# ir_transmitter.net
KiCad netlist of a schematic drawn in EAGLE
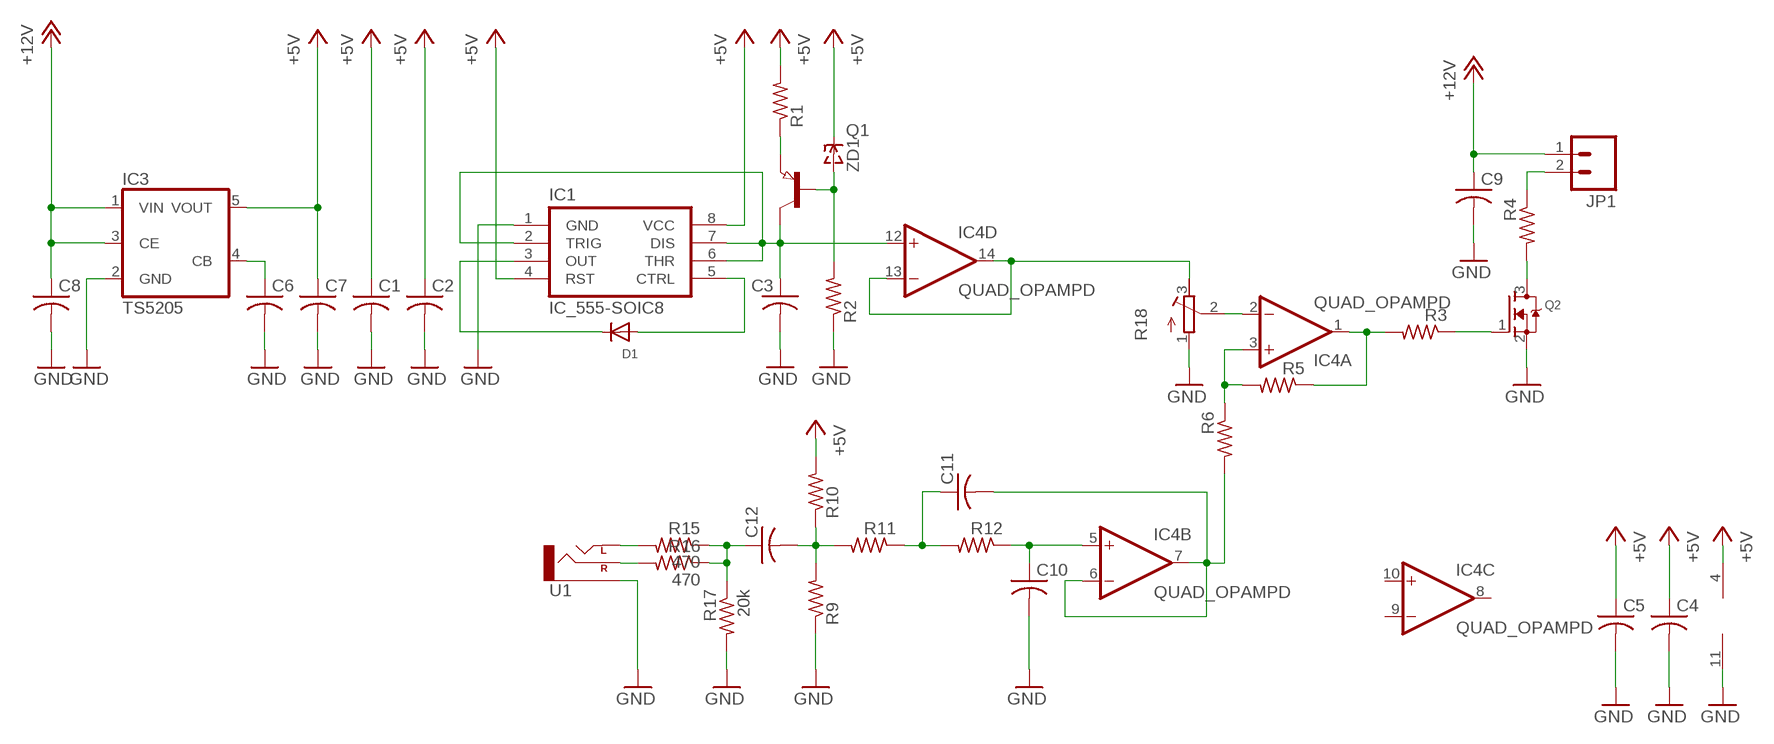
[diagram p0: schematic, sheet 1]

(export (version "E")
  (design (tool "Eeschema 10.0.6"))
  (components
    (comp (ref "C1")
      (value "C-USC1206")
      (footprint "eagle-import:C1206")
      (libsource (lib "eagle-import") (part "C-USC1206"))
    )
    (comp (ref "C2")
      (value "C-USC1206")
      (footprint "eagle-import:C1206")
      (libsource (lib "eagle-import") (part "C-USC1206"))
    )
    (comp (ref "C3")
      (value "C-USC1206")
      (footprint "eagle-import:C1206")
      (libsource (lib "eagle-import") (part "C-USC1206"))
    )
    (comp (ref "C4")
      (value "C-USC1206")
      (footprint "eagle-import:C1206")
      (libsource (lib "eagle-import") (part "C-USC1206"))
    )
    (comp (ref "C5")
      (value "C-USC1206")
      (footprint "eagle-import:C1206")
      (libsource (lib "eagle-import") (part "C-USC1206"))
    )
    (comp (ref "C6")
      (value "C-USC1206")
      (footprint "eagle-import:C1206")
      (libsource (lib "eagle-import") (part "C-USC1206"))
    )
    (comp (ref "C7")
      (value "C-USC1206")
      (footprint "eagle-import:C1206")
      (libsource (lib "eagle-import") (part "C-USC1206"))
    )
    (comp (ref "C8")
      (value "C-USC1206")
      (footprint "eagle-import:C1206")
      (libsource (lib "eagle-import") (part "C-USC1206"))
    )
    (comp (ref "C9")
      (value "C-USC1206")
      (footprint "eagle-import:C1206")
      (libsource (lib "eagle-import") (part "C-USC1206"))
    )
    (comp (ref "C10")
      (value "C-USC1206")
      (footprint "eagle-import:C1206")
      (libsource (lib "eagle-import") (part "C-USC1206"))
    )
    (comp (ref "C11")
      (value "C-USC1206")
      (footprint "eagle-import:C1206")
      (libsource (lib "eagle-import") (part "C-USC1206"))
    )
    (comp (ref "C12")
      (value "C-USC1206")
      (footprint "eagle-import:C1206")
      (libsource (lib "eagle-import") (part "C-USC1206"))
    )
    (comp (ref "D1")
      (value "DIODESOD-123")
      (footprint "eagle-import:SOD-123")
      (libsource (lib "eagle-import") (part "DIODESOD-123"))
    )
    (comp (ref "IC1")
      (value "IC_555-SOIC8")
      (footprint "eagle-import:SOIC-8")
      (libsource (lib "eagle-import") (part "IC_555-SOIC8"))
    )
    (comp (ref "IC3")
      (value "TS5205")
      (footprint "eagle-import:SOT25")
      (libsource (lib "eagle-import") (part "TS5205"))
    )
    (comp (ref "IC4")
      (value "QUAD_OPAMPD")
      (footprint "eagle-import:SO14")
      (libsource (lib "eagle-import") (part "QUAD_OPAMPD"))
    )
    (comp (ref "JP1")
      (value "M02POLAR")
      (footprint "eagle-import:MOLEX-1X2")
      (libsource (lib "eagle-import") (part "M02POLAR"))
    )
    (comp (ref "Q1")
      (value "PNP-TRANSISTOR_SOT23")
      (footprint "eagle-import:SOT23")
      (libsource (lib "eagle-import") (part "PNP-TRANSISTOR_SOT23"))
    )
    (comp (ref "Q2")
      (value "MOSFET-NREFLOW")
      (footprint "eagle-import:SOT23")
      (libsource (lib "eagle-import") (part "MOSFET-NREFLOW"))
    )
    (comp (ref "R1")
      (value "R-US_M1206")
      (footprint "eagle-import:M1206")
      (libsource (lib "eagle-import") (part "R-US_M1206"))
    )
    (comp (ref "R2")
      (value "R-US_M1206")
      (footprint "eagle-import:M1206")
      (libsource (lib "eagle-import") (part "R-US_M1206"))
    )
    (comp (ref "R3")
      (value "R-US_M1206")
      (footprint "eagle-import:M1206")
      (libsource (lib "eagle-import") (part "R-US_M1206"))
    )
    (comp (ref "R4")
      (value "R-US_M1206")
      (footprint "eagle-import:M1206")
      (libsource (lib "eagle-import") (part "R-US_M1206"))
    )
    (comp (ref "R5")
      (value "R-US_M1206")
      (footprint "eagle-import:M1206")
      (libsource (lib "eagle-import") (part "R-US_M1206"))
    )
    (comp (ref "R6")
      (value "R-US_M1206")
      (footprint "eagle-import:M1206")
      (libsource (lib "eagle-import") (part "R-US_M1206"))
    )
    (comp (ref "R9")
      (value "R-US_M1206")
      (footprint "eagle-import:M1206")
      (libsource (lib "eagle-import") (part "R-US_M1206"))
    )
    (comp (ref "R10")
      (value "R-US_M1206")
      (footprint "eagle-import:M1206")
      (libsource (lib "eagle-import") (part "R-US_M1206"))
    )
    (comp (ref "R11")
      (value "R-US_M1206")
      (footprint "eagle-import:M1206")
      (libsource (lib "eagle-import") (part "R-US_M1206"))
    )
    (comp (ref "R12")
      (value "R-US_M1206")
      (footprint "eagle-import:M1206")
      (libsource (lib "eagle-import") (part "R-US_M1206"))
    )
    (comp (ref "R15")
      (value "470")
      (footprint "eagle-import:M1206")
      (libsource (lib "eagle-import") (part "R-US_M1206"))
    )
    (comp (ref "R16")
      (value "470")
      (footprint "eagle-import:M1206")
      (libsource (lib "eagle-import") (part "R-US_M1206"))
    )
    (comp (ref "R17")
      (value "20k")
      (footprint "eagle-import:M1206")
      (libsource (lib "eagle-import") (part "R-US_M1206"))
    )
    (comp (ref "R18")
      (value "R-TRIMM3304W")
      (footprint "eagle-import:RTRIM3304W")
      (libsource (lib "eagle-import") (part "R-TRIMM3304W"))
    )
    (comp (ref "U1")
      (value "AUDIO-JACKSMD")
      (footprint "eagle-import:STEREOJACK2.5MM_SMD")
      (libsource (lib "eagle-import") (part "AUDIO-JACKSMD"))
    )
    (comp (ref "ZD1")
      (value "ZENERSOD-123")
      (footprint "eagle-import:SOD-123")
      (libsource (lib "eagle-import") (part "ZENERSOD-123"))
    )
  )
  (nets
    (net (code "1") (name "+5V") (class "Default")
      (node (ref "C1") (pin "1") (pinfunction "1_1") (pintype "passive"))
      (node (ref "C2") (pin "1") (pinfunction "1_1") (pintype "passive"))
      (node (ref "C4") (pin "1") (pinfunction "1_1") (pintype "passive"))
      (node (ref "C5") (pin "1") (pinfunction "1_1") (pintype "passive"))
      (node (ref "C7") (pin "1") (pinfunction "1_1") (pintype "passive"))
      (node (ref "IC1") (pin "4") (pinfunction "RST_4") (pintype "input"))
      (node (ref "IC1") (pin "8") (pinfunction "VCC_8") (pintype "power_in"))
      (node (ref "IC3") (pin "5") (pinfunction "VOUT_5") (pintype "passive"))
      (node (ref "IC4") (pin "4") (pinfunction "V+_4") (pintype "power_in"))
      (node (ref "R1") (pin "2") (pinfunction "2_2") (pintype "passive"))
      (node (ref "R10") (pin "2") (pinfunction "2_2") (pintype "passive"))
      (node (ref "ZD1") (pin "C") (pinfunction "C_C") (pintype "passive"))
    )
    (net (code "2") (name "+12V") (class "Default")
      (node (ref "C8") (pin "1") (pinfunction "1_1") (pintype "passive"))
      (node (ref "C9") (pin "1") (pinfunction "1_1") (pintype "passive"))
      (node (ref "IC3") (pin "1") (pinfunction "VIN_1") (pintype "input"))
      (node (ref "IC3") (pin "3") (pinfunction "CE_3") (pintype "input"))
      (node (ref "JP1") (pin "1") (pinfunction "1_1") (pintype "passive"))
    )
    (net (code "3") (name "GND") (class "Default")
      (node (ref "C1") (pin "2") (pinfunction "2_2") (pintype "passive"))
      (node (ref "C10") (pin "2") (pinfunction "2_2") (pintype "passive"))
      (node (ref "C2") (pin "2") (pinfunction "2_2") (pintype "passive"))
      (node (ref "C3") (pin "2") (pinfunction "2_2") (pintype "passive"))
      (node (ref "C4") (pin "2") (pinfunction "2_2") (pintype "passive"))
      (node (ref "C5") (pin "2") (pinfunction "2_2") (pintype "passive"))
      (node (ref "C6") (pin "2") (pinfunction "2_2") (pintype "passive"))
      (node (ref "C7") (pin "2") (pinfunction "2_2") (pintype "passive"))
      (node (ref "C8") (pin "2") (pinfunction "2_2") (pintype "passive"))
      (node (ref "C9") (pin "2") (pinfunction "2_2") (pintype "passive"))
      (node (ref "IC1") (pin "1") (pinfunction "GND_1") (pintype "power_in"))
      (node (ref "IC3") (pin "2") (pinfunction "GND_2") (pintype "passive"))
      (node (ref "IC4") (pin "11") (pinfunction "V-_11") (pintype "power_in"))
      (node (ref "Q2") (pin "2") (pinfunction "S_2") (pintype "bidirectional"))
      (node (ref "R17") (pin "2") (pinfunction "2_2") (pintype "passive"))
      (node (ref "R18") (pin "1") (pinfunction "E_1") (pintype "passive"))
      (node (ref "R2") (pin "1") (pinfunction "1_1") (pintype "passive"))
      (node (ref "R9") (pin "1") (pinfunction "1_1") (pintype "passive"))
      (node (ref "U1") (pin "5") (pinfunction "SLEEVE_5") (pintype "bidirectional"))
    )
    (net (code "4") (name "Net-(C11-Pad1)") (class "Default")
      (node (ref "C11") (pin "1") (pinfunction "1_1") (pintype "passive"))
      (node (ref "R11") (pin "1") (pinfunction "1_1") (pintype "passive"))
      (node (ref "R12") (pin "2") (pinfunction "2_2") (pintype "passive"))
    )
    (net (code "5") (name "Net-(C12-Pad1)") (class "Default")
      (node (ref "C12") (pin "1") (pinfunction "1_1") (pintype "passive"))
      (node (ref "R15") (pin "1") (pinfunction "1_1") (pintype "passive"))
      (node (ref "R16") (pin "1") (pinfunction "1_1") (pintype "passive"))
      (node (ref "R17") (pin "1") (pinfunction "1_1") (pintype "passive"))
    )
    (net (code "6") (name "Net-(C12-Pad2)") (class "Default")
      (node (ref "C12") (pin "2") (pinfunction "2_2") (pintype "passive"))
      (node (ref "R10") (pin "1") (pinfunction "1_1") (pintype "passive"))
      (node (ref "R11") (pin "2") (pinfunction "2_2") (pintype "passive"))
      (node (ref "R9") (pin "2") (pinfunction "2_2") (pintype "passive"))
    )
    (net (code "7") (name "Net-(IC1-CTRL)") (class "Default")
      (node (ref "D1") (pin "A") (pinfunction "A_A") (pintype "passive"))
      (node (ref "IC1") (pin "5") (pinfunction "CTRL_5") (pintype "power_in"))
    )
    (net (code "8") (name "Net-(IC1-DIS)") (class "Default")
      (node (ref "C3") (pin "1") (pinfunction "1_1") (pintype "passive"))
      (node (ref "IC1") (pin "2") (pinfunction "TRIG_2") (pintype "input"))
      (node (ref "IC1") (pin "6") (pinfunction "THR_6") (pintype "input"))
      (node (ref "IC1") (pin "7") (pinfunction "DIS_7") (pintype "input"))
      (node (ref "IC4") (pin "12") (pinfunction "+IN_12") (pintype "input"))
      (node (ref "Q1") (pin "3") (pinfunction "C_3") (pintype "passive"))
    )
    (net (code "9") (name "Net-(IC1-OUT)") (class "Default")
      (node (ref "D1") (pin "C") (pinfunction "C_C") (pintype "passive"))
      (node (ref "IC1") (pin "3") (pinfunction "OUT_3") (pintype "output"))
    )
    (net (code "10") (name "Net-(IC3-CB)") (class "Default")
      (node (ref "C6") (pin "1") (pinfunction "1_1") (pintype "passive"))
      (node (ref "IC3") (pin "4") (pinfunction "CB_4") (pintype "input"))
    )
    (net (code "11") (name "Net-(IC4A-+IN)") (class "Default")
      (node (ref "IC4") (pin "3") (pinfunction "+IN_3") (pintype "input"))
      (node (ref "R5") (pin "2") (pinfunction "2_2") (pintype "passive"))
      (node (ref "R6") (pin "1") (pinfunction "1_1") (pintype "passive"))
    )
    (net (code "12") (name "Net-(IC4A--IN)") (class "Default")
      (node (ref "IC4") (pin "2") (pinfunction "-IN_2") (pintype "input"))
      (node (ref "R18") (pin "2") (pinfunction "S_2") (pintype "passive"))
    )
    (net (code "13") (name "Net-(IC4A-OUT)") (class "Default")
      (node (ref "IC4") (pin "1") (pinfunction "OUT_1") (pintype "output"))
      (node (ref "R3") (pin "2") (pinfunction "2_2") (pintype "passive"))
      (node (ref "R5") (pin "1") (pinfunction "1_1") (pintype "passive"))
    )
    (net (code "14") (name "Net-(IC4B-+IN)") (class "Default")
      (node (ref "C10") (pin "1") (pinfunction "1_1") (pintype "passive"))
      (node (ref "IC4") (pin "5") (pinfunction "+IN_5") (pintype "input"))
      (node (ref "R12") (pin "1") (pinfunction "1_1") (pintype "passive"))
    )
    (net (code "15") (name "Net-(IC4B--IN)") (class "Default")
      (node (ref "C11") (pin "2") (pinfunction "2_2") (pintype "passive"))
      (node (ref "IC4") (pin "6") (pinfunction "-IN_6") (pintype "input"))
      (node (ref "IC4") (pin "7") (pinfunction "OUT_7") (pintype "output"))
      (node (ref "R6") (pin "2") (pinfunction "2_2") (pintype "passive"))
    )
    (net (code "16") (name "Net-(IC4D--IN)") (class "Default")
      (node (ref "IC4") (pin "13") (pinfunction "-IN_13") (pintype "input"))
      (node (ref "IC4") (pin "14") (pinfunction "OUT_14") (pintype "output"))
      (node (ref "R18") (pin "3") (pinfunction "A_3") (pintype "passive"))
    )
    (net (code "17") (name "Net-(JP1-Pad2)") (class "Default")
      (node (ref "JP1") (pin "2") (pinfunction "2_2") (pintype "passive"))
      (node (ref "R4") (pin "1") (pinfunction "1_1") (pintype "passive"))
    )
    (net (code "18") (name "Net-(Q1-B)") (class "Default")
      (node (ref "Q1") (pin "1") (pinfunction "B_1") (pintype "passive"))
      (node (ref "R2") (pin "2") (pinfunction "2_2") (pintype "passive"))
      (node (ref "ZD1") (pin "A") (pinfunction "A_A") (pintype "passive"))
    )
    (net (code "19") (name "Net-(Q1-E)") (class "Default")
      (node (ref "Q1") (pin "2") (pinfunction "E_2") (pintype "passive"))
      (node (ref "R1") (pin "1") (pinfunction "1_1") (pintype "passive"))
    )
    (net (code "20") (name "Net-(Q2-D)") (class "Default")
      (node (ref "Q2") (pin "3") (pinfunction "D_3") (pintype "bidirectional"))
      (node (ref "R4") (pin "2") (pinfunction "2_2") (pintype "passive"))
    )
    (net (code "21") (name "Net-(Q2-G)") (class "Default")
      (node (ref "Q2") (pin "1") (pinfunction "G_1") (pintype "bidirectional"))
      (node (ref "R3") (pin "1") (pinfunction "1_1") (pintype "passive"))
    )
    (net (code "22") (name "Net-(U1-LEFT)") (class "Default")
      (node (ref "R15") (pin "2") (pinfunction "2_2") (pintype "passive"))
      (node (ref "U1") (pin "1") (pinfunction "LEFT_1") (pintype "bidirectional"))
    )
    (net (code "23") (name "Net-(U1-RIGHT)") (class "Default")
      (node (ref "R16") (pin "2") (pinfunction "2_2") (pintype "passive"))
      (node (ref "U1") (pin "4") (pinfunction "RIGHT_4") (pintype "bidirectional"))
    )
    (net (code "24") (name "unconnected-(IC4C-+IN-Pad10)") (class "Default")
      (node (ref "IC4") (pin "10") (pinfunction "+IN_10") (pintype "input"))
    )
    (net (code "25") (name "unconnected-(IC4C--IN-Pad9)") (class "Default")
      (node (ref "IC4") (pin "9") (pinfunction "-IN_9") (pintype "input"))
    )
    (net (code "26") (name "unconnected-(IC4C-OUT-Pad8)") (class "Default")
      (node (ref "IC4") (pin "8") (pinfunction "OUT_8") (pintype "output"))
    )
  )
)
